# LEDSequencer.net
KiCad netlist of a schematic drawn in Altium Designer
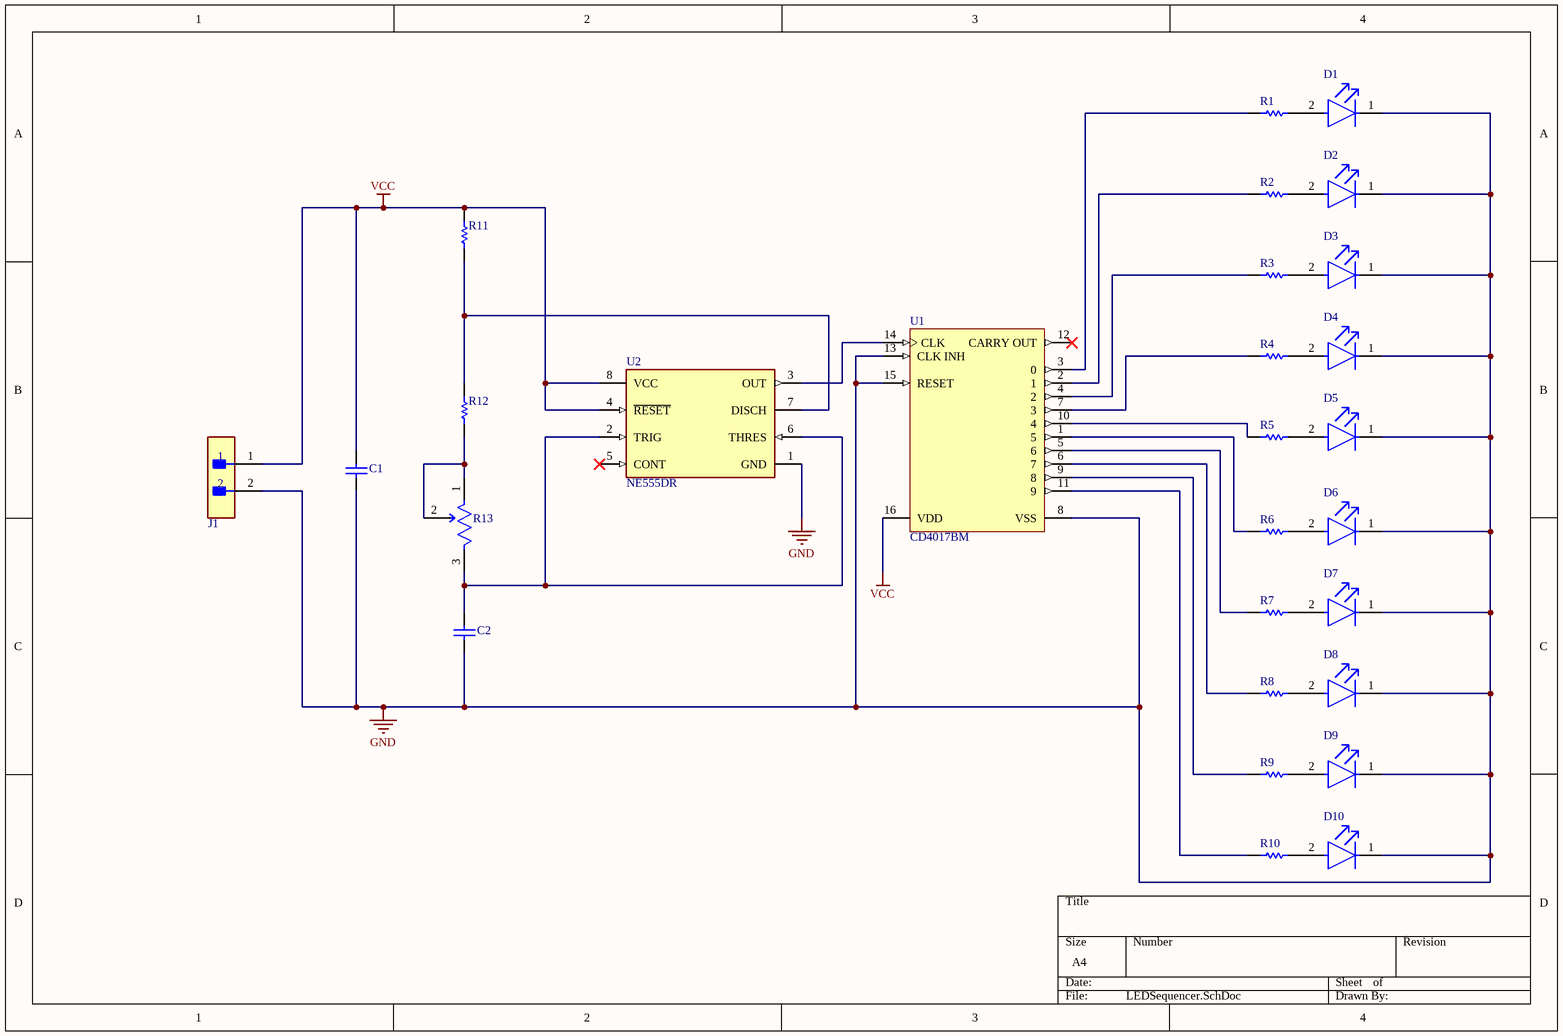
[diagram p0: LEDSequencer.SchDoc]

(export (version "E")
  (design (tool "Eeschema 10.0.6"))
  (components
    (comp (ref "C1")
      (value "1 uF")
      (footprint "CAPC2013X135X45LL10T25")
      (fields (field (name "MANUFACTURER") "Murata") (field (name "PART NUMBER") "GRM21BR71H105KA12L"))
      (libsource (lib "Altium Content Vault") (part "CAP"))
    )
    (comp (ref "C2")
      (value "1 uF")
      (footprint "CAPC2013X135X45LL10T25")
      (fields (field (name "MANUFACTURER") "Murata") (field (name "PART NUMBER") "GRM21BR71H105KA12L"))
      (libsource (lib "Altium Content Vault") (part "CAP"))
    )
    (comp (ref "D1")
      (value "HLMP-1301")
      (footprint "FP-HLMP-1301-MFG")
      (description "LED RED DIFFUSED T-1 T/H")
      (fields
        (field (name "OCTOPART") "https://octopart.com/hlmp-1301-broadcom-71130345")
        (field (name "MANUFACTURER") "Broadcom")
      )
      (libsource (lib "Altium Content Vault") (part "8706943c75ba83719d021d2fdc84c58"))
    )
    (comp (ref "D2")
      (value "HLMP-1301")
      (footprint "FP-HLMP-1301-MFG")
      (description "LED RED DIFFUSED T-1 T/H")
      (fields
        (field (name "OCTOPART") "https://octopart.com/hlmp-1301-broadcom-71130345")
        (field (name "MANUFACTURER") "Broadcom")
      )
      (libsource (lib "Altium Content Vault") (part "8706943c75ba83719d021d2fdc84c58"))
    )
    (comp (ref "D3")
      (value "HLMP-1301")
      (footprint "FP-HLMP-1301-MFG")
      (description "LED RED DIFFUSED T-1 T/H")
      (fields
        (field (name "OCTOPART") "https://octopart.com/hlmp-1301-broadcom-71130345")
        (field (name "MANUFACTURER") "Broadcom")
      )
      (libsource (lib "Altium Content Vault") (part "8706943c75ba83719d021d2fdc84c58"))
    )
    (comp (ref "D4")
      (value "HLMP-1301")
      (footprint "FP-HLMP-1301-MFG")
      (description "LED RED DIFFUSED T-1 T/H")
      (fields
        (field (name "OCTOPART") "https://octopart.com/hlmp-1301-broadcom-71130345")
        (field (name "MANUFACTURER") "Broadcom")
      )
      (libsource (lib "Altium Content Vault") (part "8706943c75ba83719d021d2fdc84c58"))
    )
    (comp (ref "D5")
      (value "HLMP-1301")
      (footprint "FP-HLMP-1301-MFG")
      (description "LED RED DIFFUSED T-1 T/H")
      (fields
        (field (name "OCTOPART") "https://octopart.com/hlmp-1301-broadcom-71130345")
        (field (name "MANUFACTURER") "Broadcom")
      )
      (libsource (lib "Altium Content Vault") (part "8706943c75ba83719d021d2fdc84c58"))
    )
    (comp (ref "D6")
      (value "HLMP-1301")
      (footprint "FP-HLMP-1301-MFG")
      (description "LED RED DIFFUSED T-1 T/H")
      (fields
        (field (name "OCTOPART") "https://octopart.com/hlmp-1301-broadcom-71130345")
        (field (name "MANUFACTURER") "Broadcom")
      )
      (libsource (lib "Altium Content Vault") (part "8706943c75ba83719d021d2fdc84c58"))
    )
    (comp (ref "D7")
      (value "HLMP-1301")
      (footprint "FP-HLMP-1301-MFG")
      (description "LED RED DIFFUSED T-1 T/H")
      (fields
        (field (name "OCTOPART") "https://octopart.com/hlmp-1301-broadcom-71130345")
        (field (name "MANUFACTURER") "Broadcom")
      )
      (libsource (lib "Altium Content Vault") (part "8706943c75ba83719d021d2fdc84c58"))
    )
    (comp (ref "D8")
      (value "HLMP-1301")
      (footprint "FP-HLMP-1301-MFG")
      (description "LED RED DIFFUSED T-1 T/H")
      (fields
        (field (name "OCTOPART") "https://octopart.com/hlmp-1301-broadcom-71130345")
        (field (name "MANUFACTURER") "Broadcom")
      )
      (libsource (lib "Altium Content Vault") (part "8706943c75ba83719d021d2fdc84c58"))
    )
    (comp (ref "D9")
      (value "HLMP-1301")
      (footprint "FP-HLMP-1301-MFG")
      (description "LED RED DIFFUSED T-1 T/H")
      (fields
        (field (name "OCTOPART") "https://octopart.com/hlmp-1301-broadcom-71130345")
        (field (name "MANUFACTURER") "Broadcom")
      )
      (libsource (lib "Altium Content Vault") (part "8706943c75ba83719d021d2fdc84c58"))
    )
    (comp (ref "D10")
      (value "HLMP-1301")
      (footprint "FP-HLMP-1301-MFG")
      (description "LED RED DIFFUSED T-1 T/H")
      (fields
        (field (name "OCTOPART") "https://octopart.com/hlmp-1301-broadcom-71130345")
        (field (name "MANUFACTURER") "Broadcom")
      )
      (libsource (lib "Altium Content Vault") (part "8706943c75ba83719d021d2fdc84c58"))
    )
    (comp (ref "J1")
      (value "M20-9990245")
      (footprint "FP-M20-9990245-MFG")
      (description "CONN HEADER VERT 2POS 2.54MM")
      (fields (field (name "VOLTAGE") "50V"))
      (libsource (lib "Altium Content Vault") (part "3bc925449376181038e59eaffc5286c"))
    )
    (comp (ref "R1")
      (value "RC0805FR-071KL")
      (footprint "RESC2013X60X35ML10T20")
      (description "Chip Resistor, 1 KOhm, +/- 1%, 125 mW, -55 to 155 degC, 0805 (2012 Metric), RoHS, Tape and Reel")
      (fields (field (name "TOLERANCE") "1%") (field (name "MANUFACTURER") "Yageo"))
      (libsource (lib "Altium Content Vault") (part "RES-2"))
    )
    (comp (ref "R2")
      (value "RC0805FR-071KL")
      (footprint "RESC2013X60X35ML10T20")
      (description "Chip Resistor, 1 KOhm, +/- 1%, 125 mW, -55 to 155 degC, 0805 (2012 Metric), RoHS, Tape and Reel")
      (fields (field (name "TOLERANCE") "1%") (field (name "MANUFACTURER") "Yageo"))
      (libsource (lib "Altium Content Vault") (part "RES-2"))
    )
    (comp (ref "R3")
      (value "RC0805FR-071KL")
      (footprint "RESC2013X60X35ML10T20")
      (description "Chip Resistor, 1 KOhm, +/- 1%, 125 mW, -55 to 155 degC, 0805 (2012 Metric), RoHS, Tape and Reel")
      (fields (field (name "TOLERANCE") "1%") (field (name "MANUFACTURER") "Yageo"))
      (libsource (lib "Altium Content Vault") (part "RES-2"))
    )
    (comp (ref "R4")
      (value "RC0805FR-071KL")
      (footprint "RESC2013X60X35ML10T20")
      (description "Chip Resistor, 1 KOhm, +/- 1%, 125 mW, -55 to 155 degC, 0805 (2012 Metric), RoHS, Tape and Reel")
      (fields (field (name "TOLERANCE") "1%") (field (name "MANUFACTURER") "Yageo"))
      (libsource (lib "Altium Content Vault") (part "RES-2"))
    )
    (comp (ref "R5")
      (value "RC0805FR-071KL")
      (footprint "RESC2013X60X35ML10T20")
      (description "Chip Resistor, 1 KOhm, +/- 1%, 125 mW, -55 to 155 degC, 0805 (2012 Metric), RoHS, Tape and Reel")
      (fields (field (name "TOLERANCE") "1%") (field (name "MANUFACTURER") "Yageo"))
      (libsource (lib "Altium Content Vault") (part "RES-2"))
    )
    (comp (ref "R6")
      (value "RC0805FR-071KL")
      (footprint "RESC2013X60X35ML10T20")
      (description "Chip Resistor, 1 KOhm, +/- 1%, 125 mW, -55 to 155 degC, 0805 (2012 Metric), RoHS, Tape and Reel")
      (fields (field (name "TOLERANCE") "1%") (field (name "MANUFACTURER") "Yageo"))
      (libsource (lib "Altium Content Vault") (part "RES-2"))
    )
    (comp (ref "R7")
      (value "RC0805FR-071KL")
      (footprint "RESC2013X60X35ML10T20")
      (description "Chip Resistor, 1 KOhm, +/- 1%, 125 mW, -55 to 155 degC, 0805 (2012 Metric), RoHS, Tape and Reel")
      (fields (field (name "TOLERANCE") "1%") (field (name "MANUFACTURER") "Yageo"))
      (libsource (lib "Altium Content Vault") (part "RES-2"))
    )
    (comp (ref "R8")
      (value "RC0805FR-071KL")
      (footprint "RESC2013X60X35ML10T20")
      (description "Chip Resistor, 1 KOhm, +/- 1%, 125 mW, -55 to 155 degC, 0805 (2012 Metric), RoHS, Tape and Reel")
      (fields (field (name "TOLERANCE") "1%") (field (name "MANUFACTURER") "Yageo"))
      (libsource (lib "Altium Content Vault") (part "RES-2"))
    )
    (comp (ref "R9")
      (value "RC0805FR-071KL")
      (footprint "RESC2013X60X35ML10T20")
      (description "Chip Resistor, 1 KOhm, +/- 1%, 125 mW, -55 to 155 degC, 0805 (2012 Metric), RoHS, Tape and Reel")
      (fields (field (name "TOLERANCE") "1%") (field (name "MANUFACTURER") "Yageo"))
      (libsource (lib "Altium Content Vault") (part "RES-2"))
    )
    (comp (ref "R10")
      (value "RC0805FR-071KL")
      (footprint "RESC2013X60X35ML10T20")
      (description "Chip Resistor, 1 KOhm, +/- 1%, 125 mW, -55 to 155 degC, 0805 (2012 Metric), RoHS, Tape and Reel")
      (fields (field (name "TOLERANCE") "1%") (field (name "MANUFACTURER") "Yageo"))
      (libsource (lib "Altium Content Vault") (part "RES-2"))
    )
    (comp (ref "R11")
      (value "2.2 k")
      (footprint "RESC2013X60X35ML10T20")
      (description "Chip Resistor, 1 KOhm, +/- 1%, 125 mW, -55 to 155 degC, 0805 (2012 Metric), RoHS, Tape and Reel")
      (fields (field (name "TOLERANCE") "1%") (field (name "MANUFACTURER") "Yageo"))
      (libsource (lib "Altium Content Vault") (part "RES-2"))
    )
    (comp (ref "R12")
      (value "10 k")
      (footprint "RESC2013X60X35ML10T20")
      (description "Chip Resistor, 1 KOhm, +/- 1%, 125 mW, -55 to 155 degC, 0805 (2012 Metric), RoHS, Tape and Reel")
      (fields (field (name "TOLERANCE") "1%") (field (name "MANUFACTURER") "Yageo"))
      (libsource (lib "Altium Content Vault") (part "RES-2"))
    )
    (comp (ref "R13")
      (value "50 k")
      (footprint "FP-3386P-MFG")
      (description "TRIMMER 100K OHM 0.5W PC PIN TOP")
      (fields (field (name "TOLERANCE") "10%"))
      (libsource (lib "Altium Content Vault") (part "13357d81287629c2fd191d242cfa50c"))
    )
    (comp (ref "U1")
      (value "CD4017BM")
      (footprint "D0016A_N")
      (description "CMOS Decade Counter with 10 Decoded Outputs, D0016A, TUBE")
      (fields
        (field (name "GENERIC PART NUMBER") "CD4017B")
        (field (name "MANUFACTURER") "Texas Instruments")
      )
      (libsource (lib "Altium Content Vault") (part "TI-CD4017B-16"))
    )
    (comp (ref "U2")
      (value "NE555DR")
      (footprint "FP-D0008A-IPC_A")
      (description "IC OSC SGL TIMER 100KHZ 8-SOIC")
      (libsource (lib "Altium Content Vault") (part "a29bba90211dec1890110b94dad7d53"))
    )
  )
  (nets
    (net (code "1") (name "GND") (class "Default")
      (node (ref "C1") (pin "1") (pinfunction "1_1") (pintype "passive"))
      (node (ref "C2") (pin "1") (pinfunction "1_1") (pintype "passive"))
      (node (ref "D1") (pin "1") (pinfunction "C_1") (pintype "passive"))
      (node (ref "D10") (pin "1") (pinfunction "C_1") (pintype "passive"))
      (node (ref "D2") (pin "1") (pinfunction "C_1") (pintype "passive"))
      (node (ref "D3") (pin "1") (pinfunction "C_1") (pintype "passive"))
      (node (ref "D4") (pin "1") (pinfunction "C_1") (pintype "passive"))
      (node (ref "D5") (pin "1") (pinfunction "C_1") (pintype "passive"))
      (node (ref "D6") (pin "1") (pinfunction "C_1") (pintype "passive"))
      (node (ref "D7") (pin "1") (pinfunction "C_1") (pintype "passive"))
      (node (ref "D8") (pin "1") (pinfunction "C_1") (pintype "passive"))
      (node (ref "D9") (pin "1") (pinfunction "C_1") (pintype "passive"))
      (node (ref "J1") (pin "2") (pinfunction "2_2") (pintype "passive"))
      (node (ref "U1") (pin "13") (pinfunction "CLK_INH_13") (pintype "input"))
      (node (ref "U1") (pin "15") (pinfunction "RESET_15") (pintype "input"))
      (node (ref "U1") (pin "8") (pinfunction "VSS_8") (pintype "power_in"))
      (node (ref "U2") (pin "1") (pinfunction "GND_1") (pintype "power_in"))
    )
    (net (code "2") (name "Net-(D1-A)") (class "Default")
      (node (ref "D1") (pin "2") (pinfunction "A_2") (pintype "passive"))
      (node (ref "R1") (pin "2") (pinfunction "2_2") (pintype "passive"))
    )
    (net (code "3") (name "Net-(D2-A)") (class "Default")
      (node (ref "D2") (pin "2") (pinfunction "A_2") (pintype "passive"))
      (node (ref "R2") (pin "2") (pinfunction "2_2") (pintype "passive"))
    )
    (net (code "4") (name "Net-(D3-A)") (class "Default")
      (node (ref "D3") (pin "2") (pinfunction "A_2") (pintype "passive"))
      (node (ref "R3") (pin "2") (pinfunction "2_2") (pintype "passive"))
    )
    (net (code "5") (name "Net-(D4-A)") (class "Default")
      (node (ref "D4") (pin "2") (pinfunction "A_2") (pintype "passive"))
      (node (ref "R4") (pin "2") (pinfunction "2_2") (pintype "passive"))
    )
    (net (code "6") (name "Net-(D5-A)") (class "Default")
      (node (ref "D5") (pin "2") (pinfunction "A_2") (pintype "passive"))
      (node (ref "R5") (pin "2") (pinfunction "2_2") (pintype "passive"))
    )
    (net (code "7") (name "Net-(D6-A)") (class "Default")
      (node (ref "D6") (pin "2") (pinfunction "A_2") (pintype "passive"))
      (node (ref "R6") (pin "2") (pinfunction "2_2") (pintype "passive"))
    )
    (net (code "8") (name "Net-(D7-A)") (class "Default")
      (node (ref "D7") (pin "2") (pinfunction "A_2") (pintype "passive"))
      (node (ref "R7") (pin "2") (pinfunction "2_2") (pintype "passive"))
    )
    (net (code "9") (name "Net-(D8-A)") (class "Default")
      (node (ref "D8") (pin "2") (pinfunction "A_2") (pintype "passive"))
      (node (ref "R8") (pin "2") (pinfunction "2_2") (pintype "passive"))
    )
    (net (code "10") (name "Net-(D9-A)") (class "Default")
      (node (ref "D9") (pin "2") (pinfunction "A_2") (pintype "passive"))
      (node (ref "R9") (pin "2") (pinfunction "2_2") (pintype "passive"))
    )
    (net (code "11") (name "Net-(D10-A)") (class "Default")
      (node (ref "D10") (pin "2") (pinfunction "A_2") (pintype "passive"))
      (node (ref "R10") (pin "2") (pinfunction "2_2") (pintype "passive"))
    )
    (net (code "12") (name "Net-(R13-CCW)") (class "Default")
      (node (ref "R12") (pin "1") (pinfunction "1_1") (pintype "passive"))
      (node (ref "R13") (pin "1") (pinfunction "CCW_1") (pintype "passive"))
      (node (ref "R13") (pin "2") (pinfunction "WIPER_2") (pintype "passive"))
    )
    (net (code "13") (name "Net-(R13-CW)") (class "Default")
      (node (ref "C2") (pin "2") (pinfunction "2_2") (pintype "passive"))
      (node (ref "R13") (pin "3") (pinfunction "CW_3") (pintype "passive"))
      (node (ref "U2") (pin "2") (pinfunction "TRIG_2") (pintype "input"))
      (node (ref "U2") (pin "6") (pinfunction "THRES_6") (pintype "input"))
    )
    (net (code "14") (name "Net-(U1-0)") (class "Default")
      (node (ref "R1") (pin "1") (pinfunction "1_1") (pintype "passive"))
      (node (ref "U1") (pin "3") (pinfunction "0_3") (pintype "output"))
    )
    (net (code "15") (name "Net-(U1-1)") (class "Default")
      (node (ref "R2") (pin "1") (pinfunction "1_1") (pintype "passive"))
      (node (ref "U1") (pin "2") (pinfunction "1_2") (pintype "output"))
    )
    (net (code "16") (name "Net-(U1-2)") (class "Default")
      (node (ref "R3") (pin "1") (pinfunction "1_1") (pintype "passive"))
      (node (ref "U1") (pin "4") (pinfunction "2_4") (pintype "output"))
    )
    (net (code "17") (name "Net-(U1-3)") (class "Default")
      (node (ref "R4") (pin "1") (pinfunction "1_1") (pintype "passive"))
      (node (ref "U1") (pin "7") (pinfunction "3_7") (pintype "output"))
    )
    (net (code "18") (name "Net-(U1-4)") (class "Default")
      (node (ref "R5") (pin "1") (pinfunction "1_1") (pintype "passive"))
      (node (ref "U1") (pin "10") (pinfunction "4_10") (pintype "output"))
    )
    (net (code "19") (name "Net-(U1-5)") (class "Default")
      (node (ref "R6") (pin "1") (pinfunction "1_1") (pintype "passive"))
      (node (ref "U1") (pin "1") (pinfunction "5_1") (pintype "output"))
    )
    (net (code "20") (name "Net-(U1-6)") (class "Default")
      (node (ref "R7") (pin "1") (pinfunction "1_1") (pintype "passive"))
      (node (ref "U1") (pin "5") (pinfunction "6_5") (pintype "output"))
    )
    (net (code "21") (name "Net-(U1-7)") (class "Default")
      (node (ref "R8") (pin "1") (pinfunction "1_1") (pintype "passive"))
      (node (ref "U1") (pin "6") (pinfunction "7_6") (pintype "output"))
    )
    (net (code "22") (name "Net-(U1-8)") (class "Default")
      (node (ref "R9") (pin "1") (pinfunction "1_1") (pintype "passive"))
      (node (ref "U1") (pin "9") (pinfunction "8_9") (pintype "output"))
    )
    (net (code "23") (name "Net-(U1-9)") (class "Default")
      (node (ref "R10") (pin "1") (pinfunction "1_1") (pintype "passive"))
      (node (ref "U1") (pin "11") (pinfunction "9_11") (pintype "output"))
    )
    (net (code "24") (name "Net-(U1-CLK)") (class "Default")
      (node (ref "U1") (pin "14") (pinfunction "CLK_14") (pintype "input"))
      (node (ref "U2") (pin "3") (pinfunction "OUT_3") (pintype "output"))
    )
    (net (code "25") (name "Net-(U2-DISCH)") (class "Default")
      (node (ref "R11") (pin "1") (pinfunction "1_1") (pintype "passive"))
      (node (ref "R12") (pin "2") (pinfunction "2_2") (pintype "passive"))
      (node (ref "U2") (pin "7") (pinfunction "DISCH_7") (pintype "open_collector"))
    )
    (net (code "26") (name "VCC") (class "Default")
      (node (ref "C1") (pin "2") (pinfunction "2_2") (pintype "passive"))
      (node (ref "J1") (pin "1") (pinfunction "1_1") (pintype "passive"))
      (node (ref "R11") (pin "2") (pinfunction "2_2") (pintype "passive"))
      (node (ref "U1") (pin "16") (pinfunction "VDD_16") (pintype "power_in"))
      (node (ref "U2") (pin "4") (pinfunction "~{RESET}_4") (pintype "input"))
      (node (ref "U2") (pin "8") (pinfunction "VCC_8") (pintype "power_in"))
    )
    (net (code "27") (name "unconnected-(U1-CARRY_OUT-Pad12)") (class "Default")
      (node (ref "U1") (pin "12") (pinfunction "CARRY_OUT_12") (pintype "output+no_connect"))
    )
    (net (code "28") (name "unconnected-(U2-CONT-Pad5)") (class "Default")
      (node (ref "U2") (pin "5") (pinfunction "CONT_5") (pintype "input+no_connect"))
    )
  )
)
